# tutorial.net
KiCad netlist of a schematic drawn in EAGLE
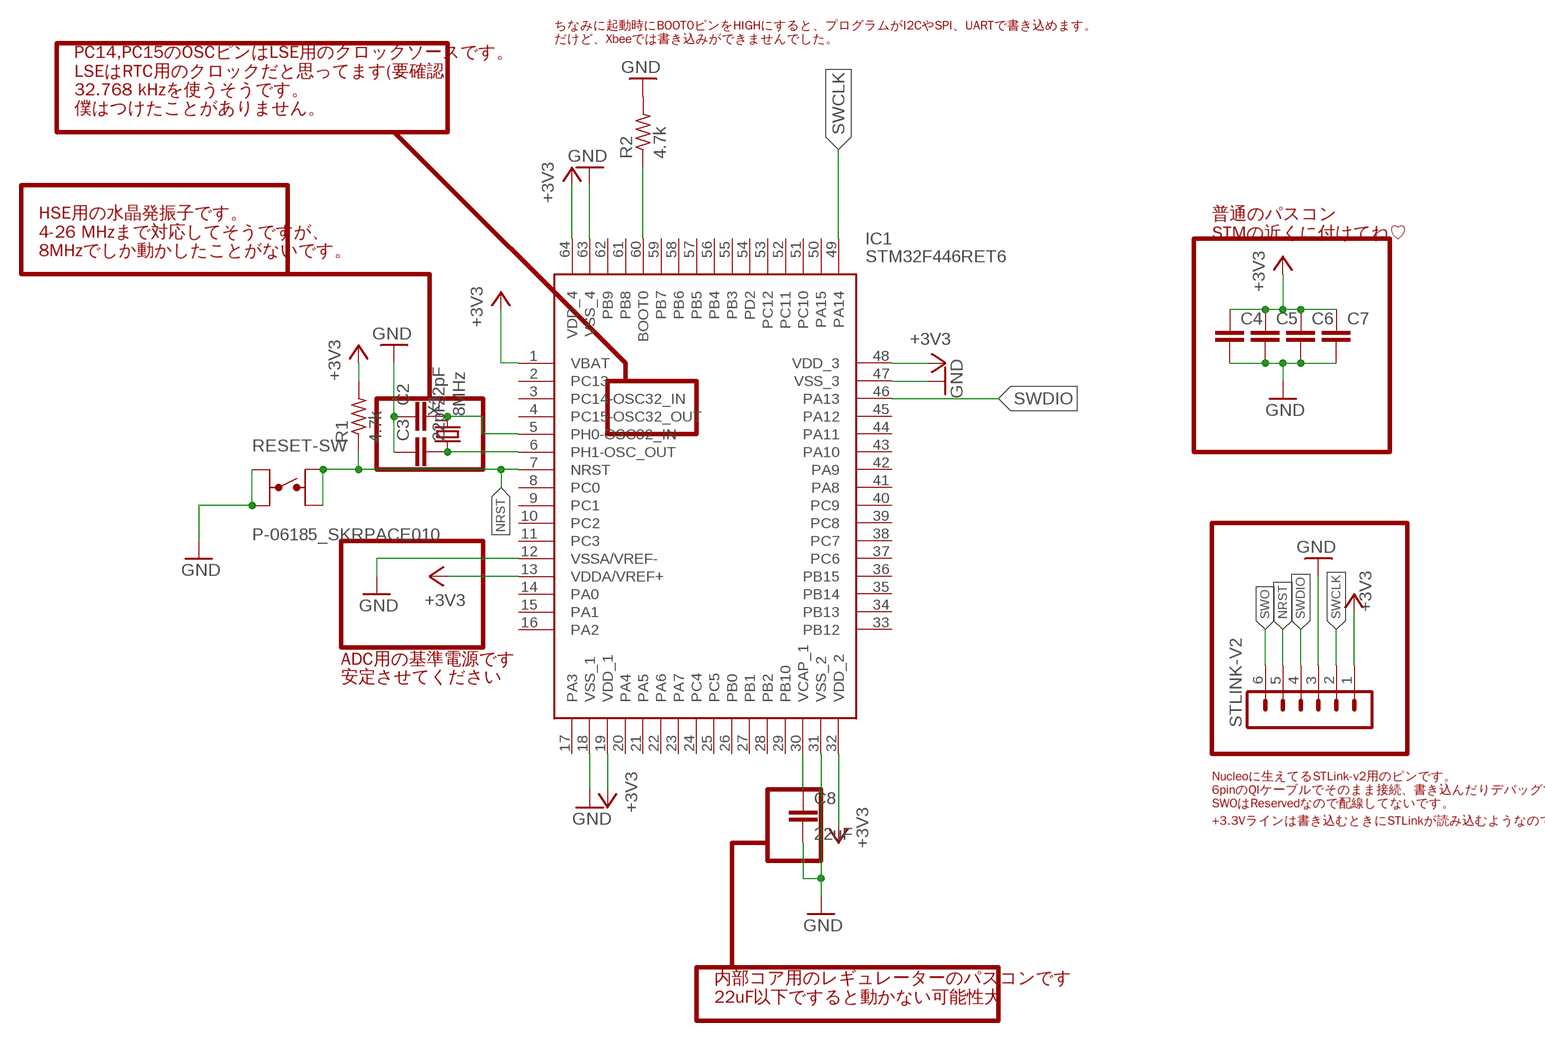
[diagram p0: schematic, sheet 1]

(export (version "E")
  (design (tool "Eeschema 10.0.6"))
  (components
    (comp (ref "C2")
      (value "22pF")
      (footprint "eagle-import:C1608")
      (libsource (lib "eagle-import") (part "C-EUC1608"))
    )
    (comp (ref "C3")
      (value "22pF")
      (footprint "eagle-import:C1608")
      (libsource (lib "eagle-import") (part "C-EUC1608"))
    )
    (comp (ref "C4")
      (value "C-EUC0805")
      (footprint "eagle-import:C0805")
      (libsource (lib "eagle-import") (part "C-EUC0805"))
    )
    (comp (ref "C5")
      (value "C-EUC0805")
      (footprint "eagle-import:C0805")
      (libsource (lib "eagle-import") (part "C-EUC0805"))
    )
    (comp (ref "C6")
      (value "C-EUC0805")
      (footprint "eagle-import:C0805")
      (libsource (lib "eagle-import") (part "C-EUC0805"))
    )
    (comp (ref "C7")
      (value "C-EUC0805")
      (footprint "eagle-import:C0805")
      (libsource (lib "eagle-import") (part "C-EUC0805"))
    )
    (comp (ref "C8")
      (value "22uF")
      (footprint "eagle-import:C0805")
      (libsource (lib "eagle-import") (part "C-EUC0805"))
    )
    (comp (ref "IC1")
      (value "STM32F446RET6")
      (footprint "eagle-import:QFP50P1200X1200X160-64N")
      (fields
        (field (name "MOUSER_PART_NUMBER") "511-STM32F446RET6")
        (field (name "RS_PART_NUMBER") "1106621P")
      )
      (libsource (lib "eagle-import") (part "STM32F446RET6"))
    )
    (comp (ref "R1")
      (value "4.7k")
      (footprint "eagle-import:M0805")
      (libsource (lib "eagle-import") (part "R-US_M0805"))
    )
    (comp (ref "R2")
      (value "4.7k")
      (footprint "eagle-import:M0805")
      (libsource (lib "eagle-import") (part "R-US_M0805"))
    )
    (comp (ref "RESET-SW")
      (value "P-06185_SKRPACE010")
      (footprint "eagle-import:SKRP")
      (libsource (lib "eagle-import") (part "P-06185_SKRPACE010"))
    )
    (comp (ref "STLINK-V2")
      (value "MA06-1")
      (footprint "eagle-import:MA06-1")
      (libsource (lib "eagle-import") (part "MA06-1"))
    )
    (comp (ref "X1")
      (value "8MHz")
      (footprint "eagle-import:HC49U-V")
      (libsource (lib "eagle-import") (part "P-08669_HUSG-12.000-20"))
    )
  )
  (nets
    (net (code "1") (name "+3V3") (class "Default")
      (node (ref "C4") (pin "1") (pinfunction "1_1") (pintype "passive"))
      (node (ref "C5") (pin "1") (pinfunction "1_1") (pintype "passive"))
      (node (ref "C6") (pin "1") (pinfunction "1_1") (pintype "passive"))
      (node (ref "C7") (pin "1") (pinfunction "1_1") (pintype "passive"))
      (node (ref "IC1") (pin "1") (pinfunction "VBAT_1") (pintype "bidirectional"))
      (node (ref "IC1") (pin "13") (pinfunction "VDDA/VREF+_13") (pintype "bidirectional"))
      (node (ref "IC1") (pin "19") (pinfunction "VDD_1_19") (pintype "bidirectional"))
      (node (ref "IC1") (pin "32") (pinfunction "VDD_2_32") (pintype "bidirectional"))
      (node (ref "IC1") (pin "48") (pinfunction "VDD_3_48") (pintype "bidirectional"))
      (node (ref "IC1") (pin "64") (pinfunction "VDD_4_64") (pintype "bidirectional"))
      (node (ref "R1") (pin "2") (pinfunction "2_2") (pintype "passive"))
      (node (ref "STLINK-V2") (pin "1") (pinfunction "1_1") (pintype "passive"))
    )
    (net (code "2") (name "GND") (class "Default")
      (node (ref "C2") (pin "1") (pinfunction "1_1") (pintype "passive"))
      (node (ref "C3") (pin "1") (pinfunction "1_1") (pintype "passive"))
      (node (ref "C4") (pin "2") (pinfunction "2_2") (pintype "passive"))
      (node (ref "C5") (pin "2") (pinfunction "2_2") (pintype "passive"))
      (node (ref "C6") (pin "2") (pinfunction "2_2") (pintype "passive"))
      (node (ref "C7") (pin "2") (pinfunction "2_2") (pintype "passive"))
      (node (ref "C8") (pin "2") (pinfunction "2_2") (pintype "passive"))
      (node (ref "IC1") (pin "12") (pinfunction "VSSA/VREF-_12") (pintype "bidirectional"))
      (node (ref "IC1") (pin "18") (pinfunction "VSS_1_18") (pintype "bidirectional"))
      (node (ref "IC1") (pin "31") (pinfunction "VSS_2_31") (pintype "bidirectional"))
      (node (ref "IC1") (pin "47") (pinfunction "VSS_3_47") (pintype "bidirectional"))
      (node (ref "IC1") (pin "63") (pinfunction "VSS_4_63") (pintype "bidirectional"))
      (node (ref "R2") (pin "2") (pinfunction "2_2") (pintype "passive"))
      (node (ref "RESET-SW") (pin "1A") (pinfunction "P$1A_1A") (pintype "bidirectional"))
      (node (ref "RESET-SW") (pin "1B") (pinfunction "P$1B_1B") (pintype "bidirectional"))
      (node (ref "STLINK-V2") (pin "3") (pinfunction "3_3") (pintype "passive"))
    )
    (net (code "3") (name "NRST") (class "Default")
      (node (ref "IC1") (pin "7") (pinfunction "NRST_7") (pintype "bidirectional"))
      (node (ref "R1") (pin "1") (pinfunction "1_1") (pintype "passive"))
      (node (ref "RESET-SW") (pin "2A") (pinfunction "P$2A_2A") (pintype "bidirectional"))
      (node (ref "RESET-SW") (pin "2B") (pinfunction "P$2B_2B") (pintype "bidirectional"))
      (node (ref "STLINK-V2") (pin "5") (pinfunction "5_5") (pintype "passive"))
    )
    (net (code "4") (name "Net-(IC1-BOOT0)") (class "Default")
      (node (ref "IC1") (pin "60") (pinfunction "BOOT0_60") (pintype "bidirectional"))
      (node (ref "R2") (pin "1") (pinfunction "1_1") (pintype "passive"))
    )
    (net (code "5") (name "Net-(IC1-PH0-OSC32_IN)") (class "Default")
      (node (ref "C2") (pin "2") (pinfunction "2_2") (pintype "passive"))
      (node (ref "IC1") (pin "5") (pinfunction "PH0-OSC32_IN_5") (pintype "bidirectional"))
      (node (ref "X1") (pin "2") (pinfunction "2_2") (pintype "passive"))
    )
    (net (code "6") (name "Net-(IC1-PH1-OSC_OUT)") (class "Default")
      (node (ref "C3") (pin "2") (pinfunction "2_2") (pintype "passive"))
      (node (ref "IC1") (pin "6") (pinfunction "PH1-OSC_OUT_6") (pintype "bidirectional"))
      (node (ref "X1") (pin "1") (pinfunction "1_1") (pintype "passive"))
    )
    (net (code "7") (name "Net-(IC1-VCAP_1)") (class "Default")
      (node (ref "C8") (pin "1") (pinfunction "1_1") (pintype "passive"))
      (node (ref "IC1") (pin "30") (pinfunction "VCAP_1_30") (pintype "bidirectional"))
    )
    (net (code "8") (name "SWCLK") (class "Default")
      (node (ref "IC1") (pin "49") (pinfunction "PA14_49") (pintype "bidirectional"))
      (node (ref "STLINK-V2") (pin "2") (pinfunction "2_2") (pintype "passive"))
    )
    (net (code "9") (name "SWDIO") (class "Default")
      (node (ref "IC1") (pin "46") (pinfunction "PA13_46") (pintype "bidirectional"))
      (node (ref "STLINK-V2") (pin "4") (pinfunction "4_4") (pintype "passive"))
    )
    (net (code "10") (name "SWO") (class "Default")
      (node (ref "STLINK-V2") (pin "6") (pinfunction "6_6") (pintype "passive"))
    )
    (net (code "11") (name "unconnected-(IC1-PA0-Pad14)") (class "Default")
      (node (ref "IC1") (pin "14") (pinfunction "PA0_14") (pintype "bidirectional"))
    )
    (net (code "12") (name "unconnected-(IC1-PA1-Pad15)") (class "Default")
      (node (ref "IC1") (pin "15") (pinfunction "PA1_15") (pintype "bidirectional"))
    )
    (net (code "13") (name "unconnected-(IC1-PA2-Pad16)") (class "Default")
      (node (ref "IC1") (pin "16") (pinfunction "PA2_16") (pintype "bidirectional"))
    )
    (net (code "14") (name "unconnected-(IC1-PA3-Pad17)") (class "Default")
      (node (ref "IC1") (pin "17") (pinfunction "PA3_17") (pintype "bidirectional"))
    )
    (net (code "15") (name "unconnected-(IC1-PA4-Pad20)") (class "Default")
      (node (ref "IC1") (pin "20") (pinfunction "PA4_20") (pintype "bidirectional"))
    )
    (net (code "16") (name "unconnected-(IC1-PA5-Pad21)") (class "Default")
      (node (ref "IC1") (pin "21") (pinfunction "PA5_21") (pintype "bidirectional"))
    )
    (net (code "17") (name "unconnected-(IC1-PA6-Pad22)") (class "Default")
      (node (ref "IC1") (pin "22") (pinfunction "PA6_22") (pintype "bidirectional"))
    )
    (net (code "18") (name "unconnected-(IC1-PA7-Pad23)") (class "Default")
      (node (ref "IC1") (pin "23") (pinfunction "PA7_23") (pintype "bidirectional"))
    )
    (net (code "19") (name "unconnected-(IC1-PA8-Pad41)") (class "Default")
      (node (ref "IC1") (pin "41") (pinfunction "PA8_41") (pintype "bidirectional"))
    )
    (net (code "20") (name "unconnected-(IC1-PA9-Pad42)") (class "Default")
      (node (ref "IC1") (pin "42") (pinfunction "PA9_42") (pintype "bidirectional"))
    )
    (net (code "21") (name "unconnected-(IC1-PA10-Pad43)") (class "Default")
      (node (ref "IC1") (pin "43") (pinfunction "PA10_43") (pintype "bidirectional"))
    )
    (net (code "22") (name "unconnected-(IC1-PA11-Pad44)") (class "Default")
      (node (ref "IC1") (pin "44") (pinfunction "PA11_44") (pintype "bidirectional"))
    )
    (net (code "23") (name "unconnected-(IC1-PA12-Pad45)") (class "Default")
      (node (ref "IC1") (pin "45") (pinfunction "PA12_45") (pintype "bidirectional"))
    )
    (net (code "24") (name "unconnected-(IC1-PA15-Pad50)") (class "Default")
      (node (ref "IC1") (pin "50") (pinfunction "PA15_50") (pintype "bidirectional"))
    )
    (net (code "25") (name "unconnected-(IC1-PB0-Pad26)") (class "Default")
      (node (ref "IC1") (pin "26") (pinfunction "PB0_26") (pintype "bidirectional"))
    )
    (net (code "26") (name "unconnected-(IC1-PB1-Pad27)") (class "Default")
      (node (ref "IC1") (pin "27") (pinfunction "PB1_27") (pintype "bidirectional"))
    )
    (net (code "27") (name "unconnected-(IC1-PB2-Pad28)") (class "Default")
      (node (ref "IC1") (pin "28") (pinfunction "PB2_28") (pintype "bidirectional"))
    )
    (net (code "28") (name "unconnected-(IC1-PB3-Pad55)") (class "Default")
      (node (ref "IC1") (pin "55") (pinfunction "PB3_55") (pintype "bidirectional"))
    )
    (net (code "29") (name "unconnected-(IC1-PB4-Pad56)") (class "Default")
      (node (ref "IC1") (pin "56") (pinfunction "PB4_56") (pintype "bidirectional"))
    )
    (net (code "30") (name "unconnected-(IC1-PB5-Pad57)") (class "Default")
      (node (ref "IC1") (pin "57") (pinfunction "PB5_57") (pintype "bidirectional"))
    )
    (net (code "31") (name "unconnected-(IC1-PB6-Pad58)") (class "Default")
      (node (ref "IC1") (pin "58") (pinfunction "PB6_58") (pintype "bidirectional"))
    )
    (net (code "32") (name "unconnected-(IC1-PB7-Pad59)") (class "Default")
      (node (ref "IC1") (pin "59") (pinfunction "PB7_59") (pintype "bidirectional"))
    )
    (net (code "33") (name "unconnected-(IC1-PB8-Pad61)") (class "Default")
      (node (ref "IC1") (pin "61") (pinfunction "PB8_61") (pintype "bidirectional"))
    )
    (net (code "34") (name "unconnected-(IC1-PB9-Pad62)") (class "Default")
      (node (ref "IC1") (pin "62") (pinfunction "PB9_62") (pintype "bidirectional"))
    )
    (net (code "35") (name "unconnected-(IC1-PB10-Pad29)") (class "Default")
      (node (ref "IC1") (pin "29") (pinfunction "PB10_29") (pintype "bidirectional"))
    )
    (net (code "36") (name "unconnected-(IC1-PB12-Pad33)") (class "Default")
      (node (ref "IC1") (pin "33") (pinfunction "PB12_33") (pintype "bidirectional"))
    )
    (net (code "37") (name "unconnected-(IC1-PB13-Pad34)") (class "Default")
      (node (ref "IC1") (pin "34") (pinfunction "PB13_34") (pintype "bidirectional"))
    )
    (net (code "38") (name "unconnected-(IC1-PB14-Pad35)") (class "Default")
      (node (ref "IC1") (pin "35") (pinfunction "PB14_35") (pintype "bidirectional"))
    )
    (net (code "39") (name "unconnected-(IC1-PB15-Pad36)") (class "Default")
      (node (ref "IC1") (pin "36") (pinfunction "PB15_36") (pintype "bidirectional"))
    )
    (net (code "40") (name "unconnected-(IC1-PC0-Pad8)") (class "Default")
      (node (ref "IC1") (pin "8") (pinfunction "PC0_8") (pintype "bidirectional"))
    )
    (net (code "41") (name "unconnected-(IC1-PC1-Pad9)") (class "Default")
      (node (ref "IC1") (pin "9") (pinfunction "PC1_9") (pintype "bidirectional"))
    )
    (net (code "42") (name "unconnected-(IC1-PC2-Pad10)") (class "Default")
      (node (ref "IC1") (pin "10") (pinfunction "PC2_10") (pintype "bidirectional"))
    )
    (net (code "43") (name "unconnected-(IC1-PC3-Pad11)") (class "Default")
      (node (ref "IC1") (pin "11") (pinfunction "PC3_11") (pintype "bidirectional"))
    )
    (net (code "44") (name "unconnected-(IC1-PC4-Pad24)") (class "Default")
      (node (ref "IC1") (pin "24") (pinfunction "PC4_24") (pintype "bidirectional"))
    )
    (net (code "45") (name "unconnected-(IC1-PC5-Pad25)") (class "Default")
      (node (ref "IC1") (pin "25") (pinfunction "PC5_25") (pintype "bidirectional"))
    )
    (net (code "46") (name "unconnected-(IC1-PC6-Pad37)") (class "Default")
      (node (ref "IC1") (pin "37") (pinfunction "PC6_37") (pintype "bidirectional"))
    )
    (net (code "47") (name "unconnected-(IC1-PC7-Pad38)") (class "Default")
      (node (ref "IC1") (pin "38") (pinfunction "PC7_38") (pintype "bidirectional"))
    )
    (net (code "48") (name "unconnected-(IC1-PC8-Pad39)") (class "Default")
      (node (ref "IC1") (pin "39") (pinfunction "PC8_39") (pintype "bidirectional"))
    )
    (net (code "49") (name "unconnected-(IC1-PC9-Pad40)") (class "Default")
      (node (ref "IC1") (pin "40") (pinfunction "PC9_40") (pintype "bidirectional"))
    )
    (net (code "50") (name "unconnected-(IC1-PC10-Pad51)") (class "Default")
      (node (ref "IC1") (pin "51") (pinfunction "PC10_51") (pintype "bidirectional"))
    )
    (net (code "51") (name "unconnected-(IC1-PC11-Pad52)") (class "Default")
      (node (ref "IC1") (pin "52") (pinfunction "PC11_52") (pintype "bidirectional"))
    )
    (net (code "52") (name "unconnected-(IC1-PC12-Pad53)") (class "Default")
      (node (ref "IC1") (pin "53") (pinfunction "PC12_53") (pintype "bidirectional"))
    )
    (net (code "53") (name "unconnected-(IC1-PC13-Pad2)") (class "Default")
      (node (ref "IC1") (pin "2") (pinfunction "PC13_2") (pintype "bidirectional"))
    )
    (net (code "54") (name "unconnected-(IC1-PC14-OSC32_IN-Pad3)") (class "Default")
      (node (ref "IC1") (pin "3") (pinfunction "PC14-OSC32_IN_3") (pintype "bidirectional"))
    )
    (net (code "55") (name "unconnected-(IC1-PC15-OSC32_OUT-Pad4)") (class "Default")
      (node (ref "IC1") (pin "4") (pinfunction "PC15-OSC32_OUT_4") (pintype "bidirectional"))
    )
    (net (code "56") (name "unconnected-(IC1-PD2-Pad54)") (class "Default")
      (node (ref "IC1") (pin "54") (pinfunction "PD2_54") (pintype "bidirectional"))
    )
  )
)
